# Sheet1.net
KiCad netlist of a schematic drawn in Altium Designer
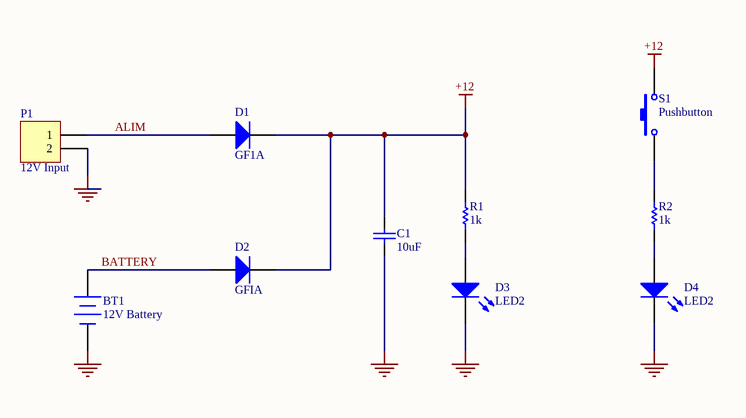
[diagram p0: Sheet1.SchDoc]

(export (version "E")
  (design (tool "Eeschema 10.0.6"))
  (components
    (comp (ref "BT1")
      (value "12V Battery")
      (footprint "BAT-2")
      (description "Multicell Battery")
      (fields (field (name "PUBLISHER") "Altium Limited"))
      (libsource (lib "Miscellaneous Devices") (part "Battery"))
    )
    (comp (ref "C1")
      (value "10uF")
      (footprint "C1206")
      (description "Capacitor (Semiconductor SIM Model)")
      (fields (field (name "PUBLISHER") "Altium Limited"))
      (libsource (lib "Miscellaneous Devices") (part "Cap Semi"))
    )
    (comp (ref "D1")
      (value "GF1A")
      (footprint "SMC")
      (description "Default Diode")
      (fields (field (name "PUBLISHER") "Altium Limited"))
      (libsource (lib "Miscellaneous Devices") (part "Diode"))
    )
    (comp (ref "D2")
      (value "GFIA")
      (footprint "SMC")
      (description "Default Diode")
      (fields (field (name "PUBLISHER") "Altium Limited"))
      (libsource (lib "Miscellaneous Devices") (part "Diode"))
    )
    (comp (ref "D3")
      (value "LED2")
      (footprint "3.2X1.6X1.1")
      (description "Typical RED, GREEN, YELLOW, AMBER GaAs LED")
      (fields (field (name "PUBLISHER") "Altium Limited"))
      (libsource (lib "Miscellaneous Devices") (part "LED2"))
    )
    (comp (ref "D4")
      (value "LED2")
      (footprint "3.2X1.6X1.1")
      (description "Typical RED, GREEN, YELLOW, AMBER GaAs LED")
      (fields (field (name "PUBLISHER") "Altium Limited"))
      (libsource (lib "Miscellaneous Devices") (part "LED2"))
    )
    (comp (ref "P1")
      (value "12V Input")
      (footprint "HDR1X2")
      (description "Header, 2-Pin")
      (fields (field (name "PUBLISHER") "Altium Limited"))
      (libsource (lib "Miscellaneous Connectors") (part "Header 2"))
    )
    (comp (ref "R1")
      (value "1k")
      (footprint "AXIAL-0.3")
      (description "Resistor")
      (fields (field (name "PUBLISHER") "Altium Limited"))
      (libsource (lib "Miscellaneous Devices") (part "Res1"))
    )
    (comp (ref "R2")
      (value "1k")
      (footprint "AXIAL-0.3")
      (description "Resistor")
      (fields (field (name "PUBLISHER") "Altium Limited"))
      (libsource (lib "Miscellaneous Devices") (part "Res1"))
    )
    (comp (ref "S1")
      (value "Pushbutton")
      (footprint "SPST-2")
      (description "Switch")
      (fields (field (name "PUBLISHER") "Altium Limited"))
      (libsource (lib "Miscellaneous Devices") (part "SW-PB"))
    )
  )
  (nets
    (net (code "1") (name "+12") (class "Default")
      (node (ref "C1") (pin "1") (pinfunction "1_1") (pintype "passive"))
      (node (ref "D1") (pin "2") (pinfunction "K_2") (pintype "passive"))
      (node (ref "D2") (pin "2") (pinfunction "K_2") (pintype "passive"))
      (node (ref "R1") (pin "2") (pinfunction "2_2") (pintype "passive"))
      (node (ref "S1") (pin "2") (pinfunction "2_2") (pintype "passive"))
    )
    (net (code "2") (name "/ALIM") (class "Default")
      (node (ref "D1") (pin "1") (pinfunction "A_1") (pintype "passive"))
      (node (ref "P1") (pin "1") (pinfunction "1_1") (pintype "passive"))
    )
    (net (code "3") (name "/BATTERY") (class "Default")
      (node (ref "BT1") (pin "1") (pinfunction "+_1") (pintype "passive"))
      (node (ref "D2") (pin "1") (pinfunction "A_1") (pintype "passive"))
    )
    (net (code "4") (name "GND") (class "Default")
      (node (ref "BT1") (pin "2") (pinfunction "-_2") (pintype "passive"))
      (node (ref "C1") (pin "2") (pinfunction "2_2") (pintype "passive"))
      (node (ref "D3") (pin "2") (pinfunction "K_2") (pintype "passive"))
      (node (ref "D4") (pin "2") (pinfunction "K_2") (pintype "passive"))
      (node (ref "P1") (pin "2") (pinfunction "2_2") (pintype "passive"))
    )
    (net (code "5") (name "Net-(D3-A)") (class "Default")
      (node (ref "D3") (pin "1") (pinfunction "A_1") (pintype "passive"))
      (node (ref "R1") (pin "1") (pinfunction "1_1") (pintype "passive"))
    )
    (net (code "6") (name "Net-(D4-A)") (class "Default")
      (node (ref "D4") (pin "1") (pinfunction "A_1") (pintype "passive"))
      (node (ref "R2") (pin "1") (pinfunction "1_1") (pintype "passive"))
    )
    (net (code "7") (name "Net-(R2-Pad2)") (class "Default")
      (node (ref "R2") (pin "2") (pinfunction "2_2") (pintype "passive"))
      (node (ref "S1") (pin "1") (pinfunction "1_1") (pintype "passive"))
    )
  )
)
